# child_easyeda.net
KiCad netlist of a schematic drawn in EasyEDA
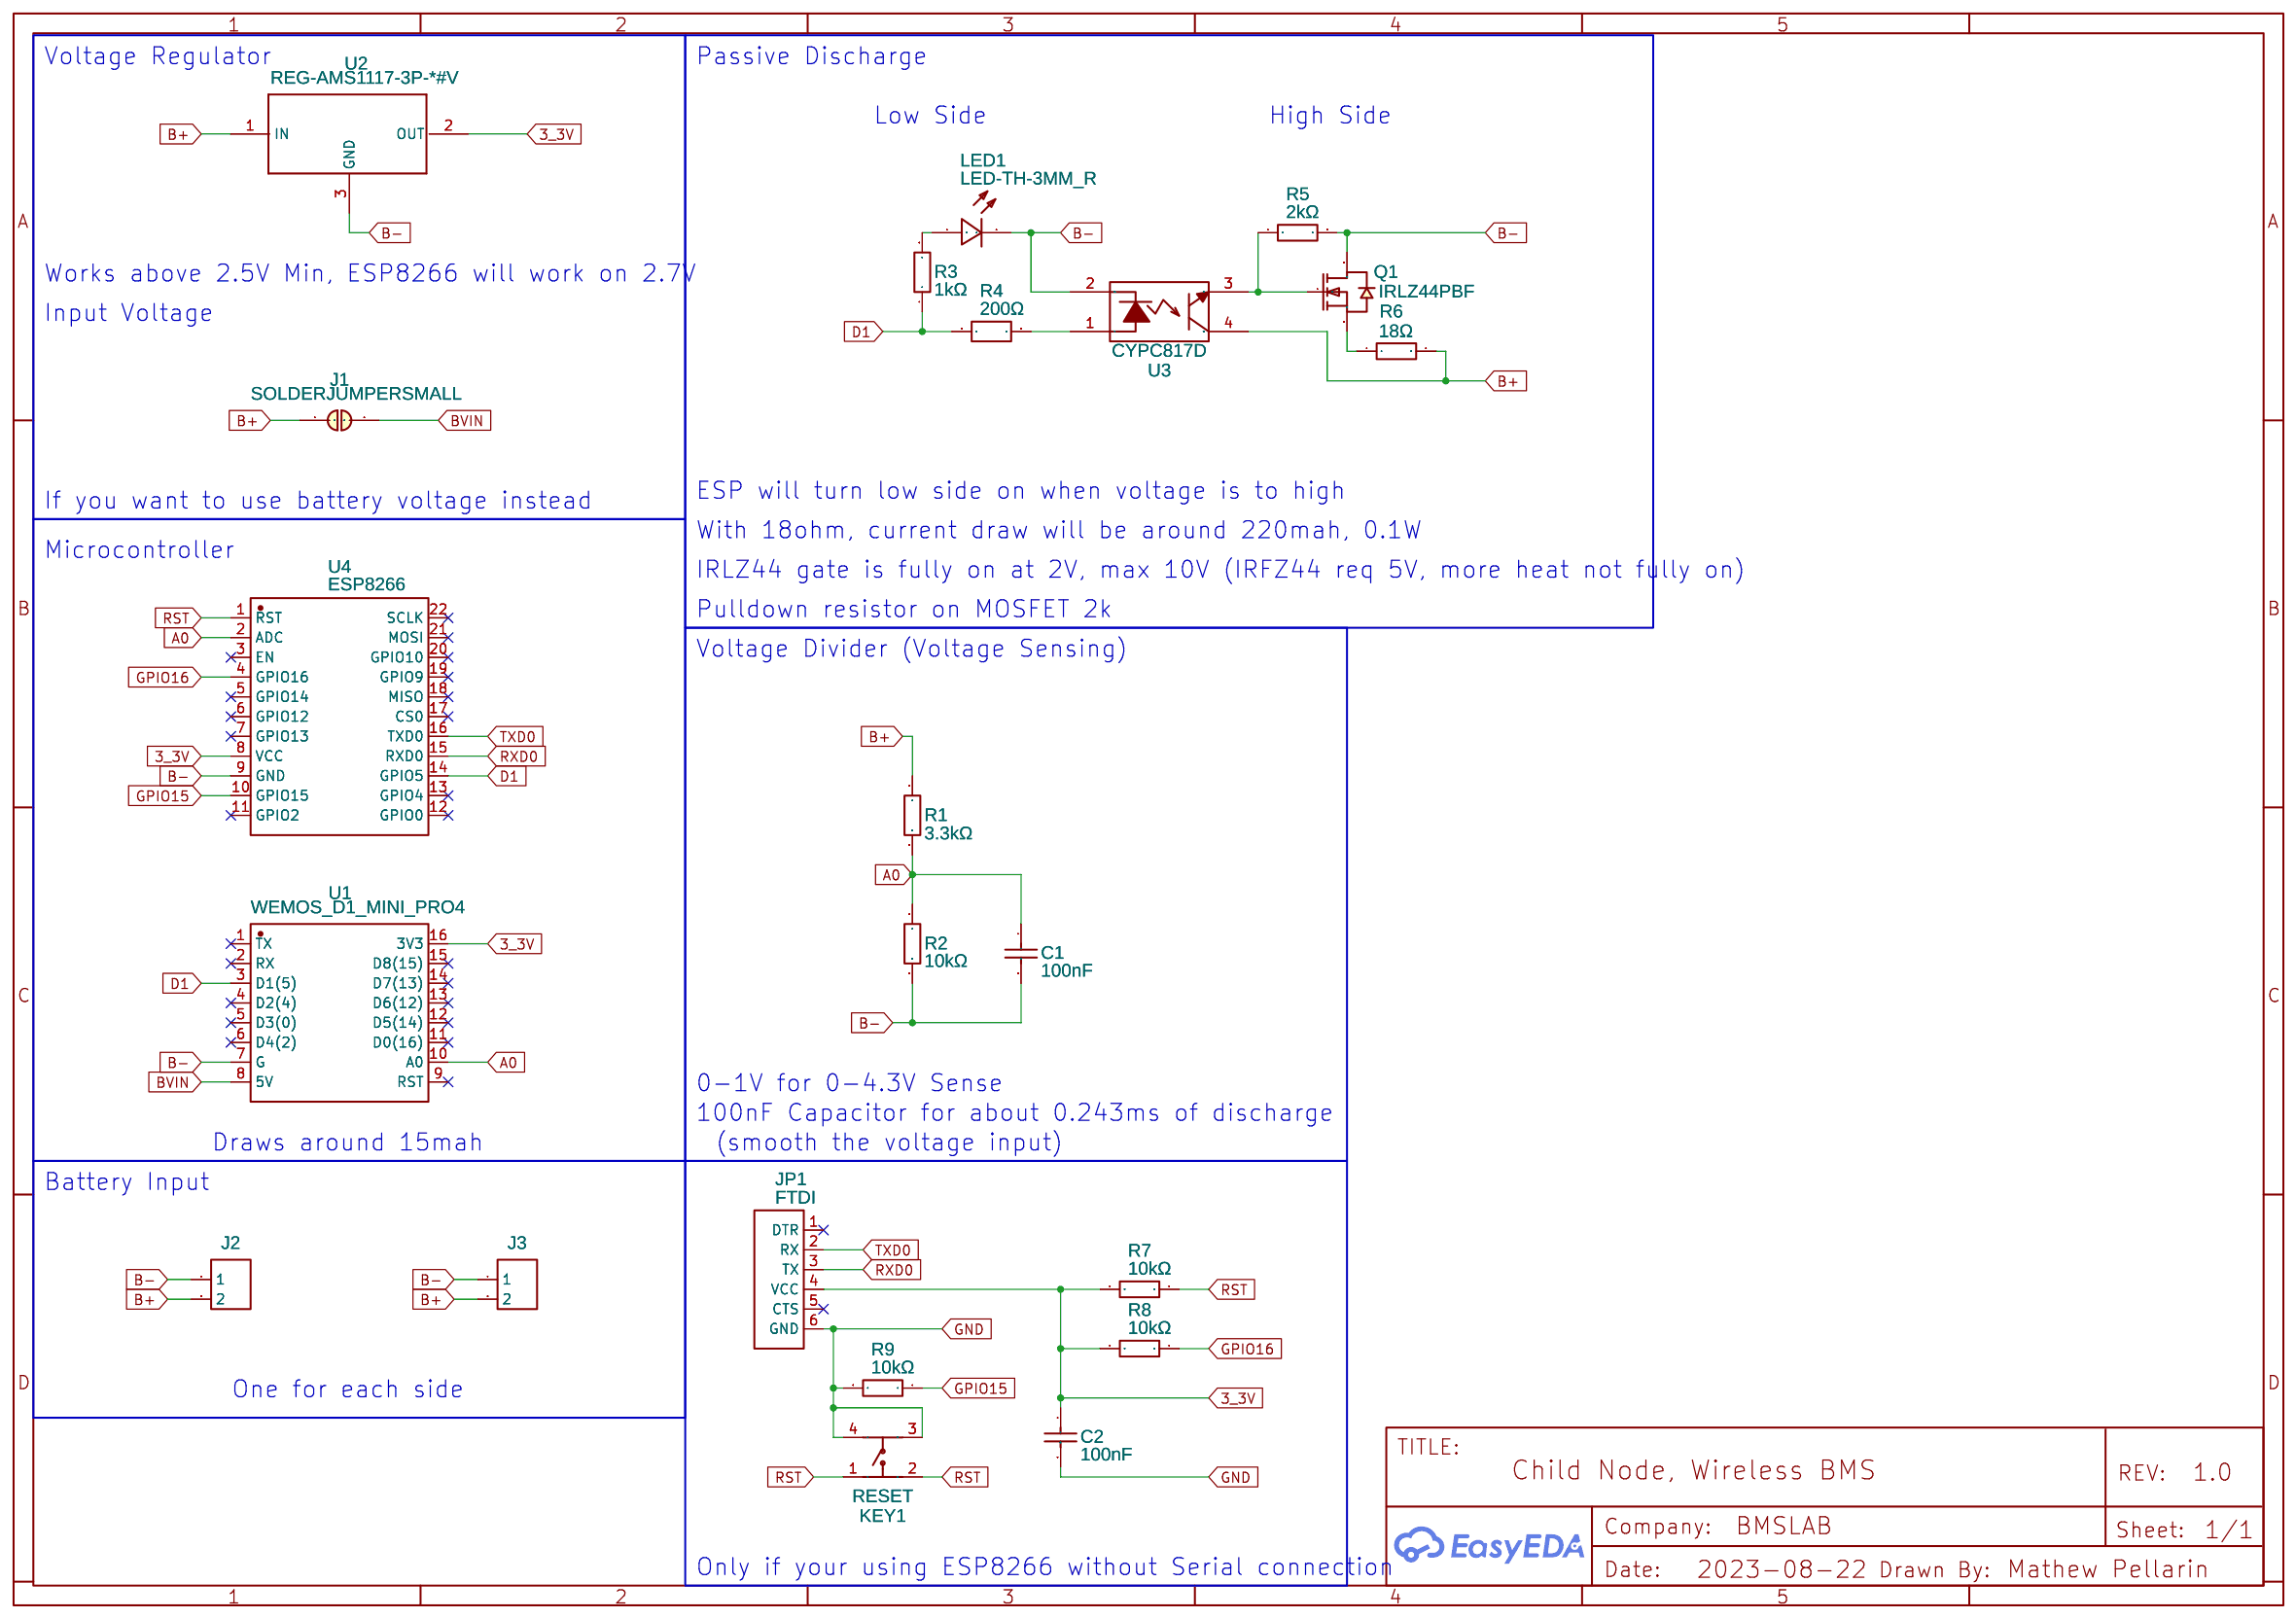
[diagram p0: schematic sheet]

(export (version "E")
  (design (tool "Eeschema 10.0.6"))
  (components
    (comp (ref "C1")
      (value "100nF")
      (fields (field (name "Manufacturer Part") "SR305C105KAR") (field (name "Manufacturer") "Kyocera AVX"))
      (libsource (lib "") (part "SR305C105KAR"))
    )
    (comp (ref "C2")
      (value "100nF")
      (fields (field (name "Manufacturer Part") "SR305C105KAR") (field (name "Manufacturer") "Kyocera AVX"))
      (libsource (lib "") (part "SR305C105KAR"))
    )
    (comp (ref "J1") (value "SOLDERJUMPERSMALL") (libsource (lib "") (part "SOLDERJUMPERSMALL")))
    (comp (ref "J2")
      (value "NO")
      (fields
        (field (name "Manufacturer Part") "Female headerHDR1X8-2.54")
        (field (name "Manufacturer") "BOOMELE")
      )
      (libsource (lib "") (part "Header-Female-2.54_1x2"))
    )
    (comp (ref "J3")
      (value "NO")
      (fields
        (field (name "Manufacturer Part") "Female headerHDR1X8-2.54")
        (field (name "Manufacturer") "BOOMELE")
      )
      (libsource (lib "") (part "Header-Female-2.54_1x2"))
    )
    (comp (ref "JP1") (value "FTDI") (libsource (lib "") (part "FTDI")))
    (comp (ref "KEY1")
      (value "RESET")
      (fields (field (name "Manufacturer Part") "button6*6*8") (field (name "Manufacturer") "ReliaPro"))
      (libsource (lib "") (part "button6*6*8"))
    )
    (comp (ref "LED1")
      (value "LED-TH-3MM_R")
      (fields (field (name "Manufacturer Part") "LED-TH-3mm_R"))
      (libsource (lib "") (part "LED-TH-3MM_R"))
    )
    (comp (ref "Q1")
      (value "IRLZ44PBF")
      (fields (field (name "Manufacturer Part") "IRLZ44PBF-VB") (field (name "Manufacturer") "VBsemi(微碧)"))
      (libsource (lib "") (part "IRLZ44PBF"))
    )
    (comp (ref "R1")
      (value "3.3kΩ")
      (fields (field (name "Manufacturer Part") "MFR-25FTE52-33K") (field (name "Manufacturer") "YAGEO(国巨)"))
      (libsource (lib "") (part "MFR-25FTE52-33K"))
    )
    (comp (ref "R2")
      (value "10kΩ")
      (fields (field (name "Manufacturer Part") "MFR-25FTE52-100K") (field (name "Manufacturer") "YAGEO(国巨)"))
      (libsource (lib "") (part "MFR-25FTE52-100K"))
    )
    (comp (ref "R3")
      (value "1kΩ")
      (fields (field (name "Manufacturer Part") "MFR50SFTE52-1K") (field (name "Manufacturer") "YAGEO(国巨)"))
      (libsource (lib "") (part "MFR50SFTE52-1K"))
    )
    (comp (ref "R4")
      (value "200Ω")
      (fields (field (name "Manufacturer Part") "CR1/4W-200Ω±5%-ST52") (field (name "Manufacturer") "VO(翔胜)"))
      (libsource (lib "") (part "CR1/4W-200Ω±5%-ST52"))
    )
    (comp (ref "R5")
      (value "2kΩ")
      (fields (field (name "Manufacturer Part") "MFR-25FTE52-2K") (field (name "Manufacturer") "YAGEO(国巨)"))
      (libsource (lib "") (part "MFR-25FTE52-2K"))
    )
    (comp (ref "R6")
      (value "18Ω")
      (fields (field (name "Manufacturer Part") "CF1/4W-18Ω±5% T") (field (name "Manufacturer") "CCO(千志电子)"))
      (libsource (lib "") (part "CF1/4W-18Ω±5% T52"))
    )
    (comp (ref "R7")
      (value "10kΩ")
      (fields (field (name "Manufacturer Part") "MFR-25FTE52-33K") (field (name "Manufacturer") "YAGEO(国巨)"))
      (libsource (lib "") (part "MFR-25FTE52-33K_1"))
    )
    (comp (ref "R8")
      (value "10kΩ")
      (fields (field (name "Manufacturer Part") "MFR-25FTE52-33K") (field (name "Manufacturer") "YAGEO(国巨)"))
      (libsource (lib "") (part "MFR-25FTE52-33K_1"))
    )
    (comp (ref "R9")
      (value "10kΩ")
      (fields (field (name "Manufacturer Part") "MFR-25FTE52-33K") (field (name "Manufacturer") "YAGEO(国巨)"))
      (libsource (lib "") (part "MFR-25FTE52-33K_1"))
    )
    (comp (ref "U1")
      (value "WEMOS_D1_MINI_PRO4")
      (fields (field (name "Manufacturer Part") "Wemos_D1_mini_Pro4"))
      (libsource (lib "") (part "WEMOS_D1_MINI_PRO4"))
    )
    (comp (ref "U2") (value "REG-AMS1117-3P-*#V") (libsource (lib "") (part "REG-AMS1117-3P-*#V")))
    (comp (ref "U3")
      (value "CYPC817D")
      (fields (field (name "Manufacturer") "OCIC(卓睿科)"))
      (libsource (lib "") (part "CYPC817D"))
    )
    (comp (ref "U4") (value "ESP8266") (libsource (lib "") (part "ESP8266")))
  )
  (nets
    (net (code "1") (name "3_3V") (class "Default")
      (node (ref "C2") (pin "1") (pinfunction "1_1") (pintype "input"))
      (node (ref "JP1") (pin "4") (pinfunction "VCC_4") (pintype "unspecified"))
      (node (ref "R7") (pin "2") (pinfunction "2_2") (pintype "unspecified"))
      (node (ref "R8") (pin "2") (pinfunction "2_2") (pintype "unspecified"))
      (node (ref "U1") (pin "16") (pinfunction "3V3_16") (pintype "unspecified"))
      (node (ref "U2") (pin "2") (pinfunction "OUT_2") (pintype "bidirectional"))
      (node (ref "U4") (pin "8") (pinfunction "VCC_8") (pintype "unspecified"))
    )
    (net (code "2") (name "A0") (class "Default")
      (node (ref "C1") (pin "1") (pinfunction "1_1") (pintype "input"))
      (node (ref "R1") (pin "2") (pinfunction "2_2") (pintype "unspecified"))
      (node (ref "R2") (pin "1") (pinfunction "1_1") (pintype "unspecified"))
      (node (ref "U1") (pin "10") (pinfunction "A0_10") (pintype "unspecified"))
      (node (ref "U4") (pin "2") (pinfunction "ADC_2") (pintype "unspecified"))
    )
    (net (code "3") (name "B+") (class "Default")
      (node (ref "J1") (pin "1") (pinfunction "1_1") (pintype "unspecified"))
      (node (ref "J2") (pin "2") (pinfunction "2_2") (pintype "input"))
      (node (ref "J3") (pin "2") (pinfunction "2_2") (pintype "input"))
      (node (ref "R1") (pin "1") (pinfunction "1_1") (pintype "unspecified"))
      (node (ref "R6") (pin "2") (pinfunction "2_2") (pintype "unspecified"))
      (node (ref "U2") (pin "1") (pinfunction "IN_1") (pintype "bidirectional"))
      (node (ref "U3") (pin "4") (pinfunction "COL_4") (pintype "unspecified"))
    )
    (net (code "4") (name "B-") (class "Default")
      (node (ref "C1") (pin "2") (pinfunction "2_2") (pintype "input"))
      (node (ref "J2") (pin "1") (pinfunction "1_1") (pintype "input"))
      (node (ref "J3") (pin "1") (pinfunction "1_1") (pintype "input"))
      (node (ref "LED1") (pin "2") (pinfunction "2_2") (pintype "unspecified"))
      (node (ref "Q1") (pin "2") (pinfunction "D_2") (pintype "unspecified"))
      (node (ref "R2") (pin "2") (pinfunction "2_2") (pintype "unspecified"))
      (node (ref "R5") (pin "2") (pinfunction "2_2") (pintype "unspecified"))
      (node (ref "U1") (pin "7") (pinfunction "G_7") (pintype "unspecified"))
      (node (ref "U2") (pin "3") (pinfunction "GND_3") (pintype "bidirectional"))
      (node (ref "U3") (pin "2") (pinfunction "CAT_2") (pintype "unspecified"))
      (node (ref "U4") (pin "9") (pinfunction "GND_9") (pintype "unspecified"))
    )
    (net (code "5") (name "BVIN") (class "Default")
      (node (ref "J1") (pin "2") (pinfunction "2_2") (pintype "unspecified"))
      (node (ref "U1") (pin "8") (pinfunction "5V_8") (pintype "unspecified"))
    )
    (net (code "6") (name "D1") (class "Default")
      (node (ref "R3") (pin "1") (pinfunction "1_1") (pintype "unspecified"))
      (node (ref "R4") (pin "1") (pinfunction "1_1") (pintype "unspecified"))
      (node (ref "U1") (pin "3") (pinfunction "D1(5)_3") (pintype "unspecified"))
      (node (ref "U4") (pin "14") (pinfunction "GPIO5_14") (pintype "unspecified"))
    )
    (net (code "7") (name "GND") (class "Default")
      (node (ref "C2") (pin "2") (pinfunction "2_2") (pintype "input"))
      (node (ref "JP1") (pin "6") (pinfunction "GND_6") (pintype "unspecified"))
      (node (ref "KEY1") (pin "3") (pinfunction "3_3") (pintype "unspecified"))
      (node (ref "KEY1") (pin "4") (pinfunction "4_4") (pintype "unspecified"))
      (node (ref "R9") (pin "2") (pinfunction "2_2") (pintype "unspecified"))
    )
    (net (code "8") (name "GPIO15") (class "Default")
      (node (ref "R9") (pin "1") (pinfunction "1_1") (pintype "unspecified"))
      (node (ref "U4") (pin "10") (pinfunction "GPIO15_10") (pintype "unspecified"))
    )
    (net (code "9") (name "GPIO16") (class "Default")
      (node (ref "R8") (pin "1") (pinfunction "1_1") (pintype "unspecified"))
      (node (ref "U4") (pin "4") (pinfunction "GPIO16_4") (pintype "unspecified"))
    )
    (net (code "10") (name "Net-(LED1-Pad1)") (class "Default")
      (node (ref "LED1") (pin "1") (pinfunction "1_1") (pintype "unspecified"))
      (node (ref "R3") (pin "2") (pinfunction "2_2") (pintype "unspecified"))
    )
    (net (code "11") (name "Net-(Q1-G)") (class "Default")
      (node (ref "Q1") (pin "1") (pinfunction "G_1") (pintype "unspecified"))
      (node (ref "R5") (pin "1") (pinfunction "1_1") (pintype "unspecified"))
      (node (ref "U3") (pin "3") (pinfunction "EM_3") (pintype "unspecified"))
    )
    (net (code "12") (name "Net-(Q1-S)") (class "Default")
      (node (ref "Q1") (pin "3") (pinfunction "S_3") (pintype "unspecified"))
      (node (ref "R6") (pin "1") (pinfunction "1_1") (pintype "unspecified"))
    )
    (net (code "13") (name "Net-(U3-AN)") (class "Default")
      (node (ref "R4") (pin "2") (pinfunction "2_2") (pintype "unspecified"))
      (node (ref "U3") (pin "1") (pinfunction "AN_1") (pintype "unspecified"))
    )
    (net (code "14") (name "RST") (class "Default")
      (node (ref "KEY1") (pin "1") (pinfunction "1_1") (pintype "unspecified"))
      (node (ref "KEY1") (pin "2") (pinfunction "2_2") (pintype "unspecified"))
      (node (ref "R7") (pin "1") (pinfunction "1_1") (pintype "unspecified"))
      (node (ref "U4") (pin "1") (pinfunction "RST_1") (pintype "unspecified"))
    )
    (net (code "15") (name "RXD0") (class "Default")
      (node (ref "JP1") (pin "3") (pinfunction "TX_3") (pintype "unspecified"))
      (node (ref "U4") (pin "15") (pinfunction "RXD0_15") (pintype "unspecified"))
    )
    (net (code "16") (name "TXD0") (class "Default")
      (node (ref "JP1") (pin "2") (pinfunction "RX_2") (pintype "unspecified"))
      (node (ref "U4") (pin "16") (pinfunction "TXD0_16") (pintype "unspecified"))
    )
    (net (code "17") (name "unconnected-(JP1-CTS-Pad5)") (class "Default")
      (node (ref "JP1") (pin "5") (pinfunction "CTS_5") (pintype "unspecified+no_connect"))
    )
    (net (code "18") (name "unconnected-(JP1-DTR-Pad1)") (class "Default")
      (node (ref "JP1") (pin "1") (pinfunction "DTR_1") (pintype "unspecified+no_connect"))
    )
    (net (code "19") (name "unconnected-(U1-D0(16)-Pad11)") (class "Default")
      (node (ref "U1") (pin "11") (pinfunction "D0(16)_11") (pintype "unspecified+no_connect"))
    )
    (net (code "20") (name "unconnected-(U1-D2(4)-Pad4)") (class "Default")
      (node (ref "U1") (pin "4") (pinfunction "D2(4)_4") (pintype "unspecified+no_connect"))
    )
    (net (code "21") (name "unconnected-(U1-D3(0)-Pad5)") (class "Default")
      (node (ref "U1") (pin "5") (pinfunction "D3(0)_5") (pintype "unspecified+no_connect"))
    )
    (net (code "22") (name "unconnected-(U1-D4(2)-Pad6)") (class "Default")
      (node (ref "U1") (pin "6") (pinfunction "D4(2)_6") (pintype "unspecified+no_connect"))
    )
    (net (code "23") (name "unconnected-(U1-D5(14)-Pad12)") (class "Default")
      (node (ref "U1") (pin "12") (pinfunction "D5(14)_12") (pintype "unspecified+no_connect"))
    )
    (net (code "24") (name "unconnected-(U1-D6(12)-Pad13)") (class "Default")
      (node (ref "U1") (pin "13") (pinfunction "D6(12)_13") (pintype "unspecified+no_connect"))
    )
    (net (code "25") (name "unconnected-(U1-D7(13)-Pad14)") (class "Default")
      (node (ref "U1") (pin "14") (pinfunction "D7(13)_14") (pintype "unspecified+no_connect"))
    )
    (net (code "26") (name "unconnected-(U1-D8(15)-Pad15)") (class "Default")
      (node (ref "U1") (pin "15") (pinfunction "D8(15)_15") (pintype "unspecified+no_connect"))
    )
    (net (code "27") (name "unconnected-(U1-RST-Pad9)") (class "Default")
      (node (ref "U1") (pin "9") (pinfunction "RST_9") (pintype "unspecified+no_connect"))
    )
    (net (code "28") (name "unconnected-(U1-RX-Pad2)") (class "Default")
      (node (ref "U1") (pin "2") (pinfunction "RX_2") (pintype "unspecified+no_connect"))
    )
    (net (code "29") (name "unconnected-(U1-TX-Pad1)") (class "Default")
      (node (ref "U1") (pin "1") (pinfunction "TX_1") (pintype "unspecified+no_connect"))
    )
    (net (code "30") (name "unconnected-(U4-CS0-Pad17)") (class "Default")
      (node (ref "U4") (pin "17") (pinfunction "CS0_17") (pintype "unspecified+no_connect"))
    )
    (net (code "31") (name "unconnected-(U4-EN-Pad3)") (class "Default")
      (node (ref "U4") (pin "3") (pinfunction "EN_3") (pintype "unspecified+no_connect"))
    )
    (net (code "32") (name "unconnected-(U4-GPIO0-Pad12)") (class "Default")
      (node (ref "U4") (pin "12") (pinfunction "GPIO0_12") (pintype "unspecified+no_connect"))
    )
    (net (code "33") (name "unconnected-(U4-GPIO2-Pad11)") (class "Default")
      (node (ref "U4") (pin "11") (pinfunction "GPIO2_11") (pintype "unspecified+no_connect"))
    )
    (net (code "34") (name "unconnected-(U4-GPIO4-Pad13)") (class "Default")
      (node (ref "U4") (pin "13") (pinfunction "GPIO4_13") (pintype "unspecified+no_connect"))
    )
    (net (code "35") (name "unconnected-(U4-GPIO9-Pad19)") (class "Default")
      (node (ref "U4") (pin "19") (pinfunction "GPIO9_19") (pintype "unspecified+no_connect"))
    )
    (net (code "36") (name "unconnected-(U4-GPIO10-Pad20)") (class "Default")
      (node (ref "U4") (pin "20") (pinfunction "GPIO10_20") (pintype "unspecified+no_connect"))
    )
    (net (code "37") (name "unconnected-(U4-GPIO12-Pad6)") (class "Default")
      (node (ref "U4") (pin "6") (pinfunction "GPIO12_6") (pintype "unspecified+no_connect"))
    )
    (net (code "38") (name "unconnected-(U4-GPIO13-Pad7)") (class "Default")
      (node (ref "U4") (pin "7") (pinfunction "GPIO13_7") (pintype "unspecified+no_connect"))
    )
    (net (code "39") (name "unconnected-(U4-GPIO14-Pad5)") (class "Default")
      (node (ref "U4") (pin "5") (pinfunction "GPIO14_5") (pintype "unspecified+no_connect"))
    )
    (net (code "40") (name "unconnected-(U4-MISO-Pad18)") (class "Default")
      (node (ref "U4") (pin "18") (pinfunction "MISO_18") (pintype "unspecified+no_connect"))
    )
    (net (code "41") (name "unconnected-(U4-MOSI-Pad21)") (class "Default")
      (node (ref "U4") (pin "21") (pinfunction "MOSI_21") (pintype "unspecified+no_connect"))
    )
    (net (code "42") (name "unconnected-(U4-SCLK-Pad22)") (class "Default")
      (node (ref "U4") (pin "22") (pinfunction "SCLK_22") (pintype "unspecified+no_connect"))
    )
  )
)
